# CMCD_and_buckmod_FINAL.net
KiCad netlist of a schematic drawn in EAGLE
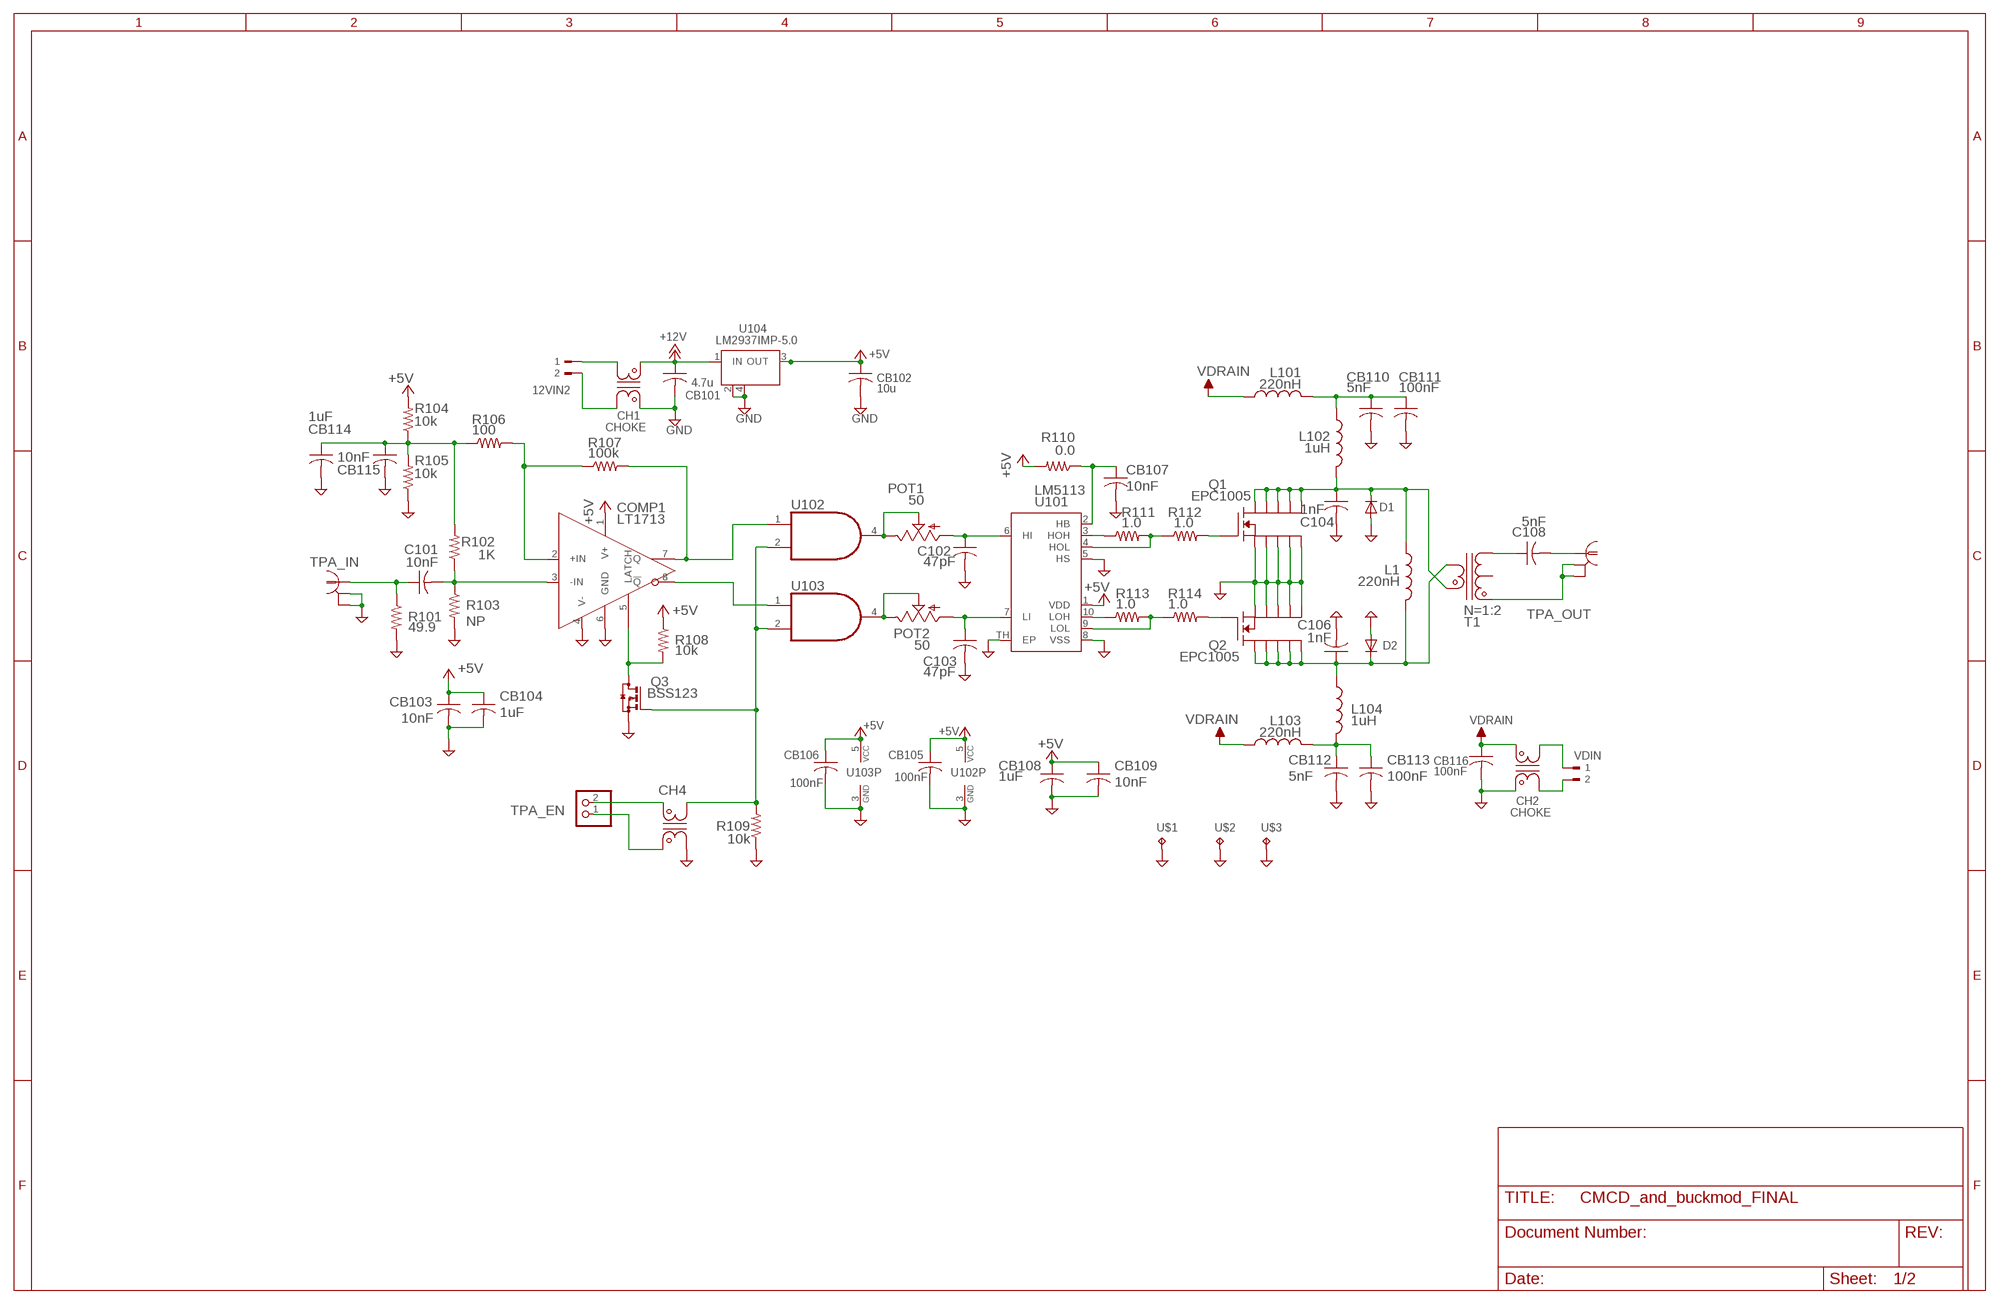
[diagram p0: schematic, sheet 1]
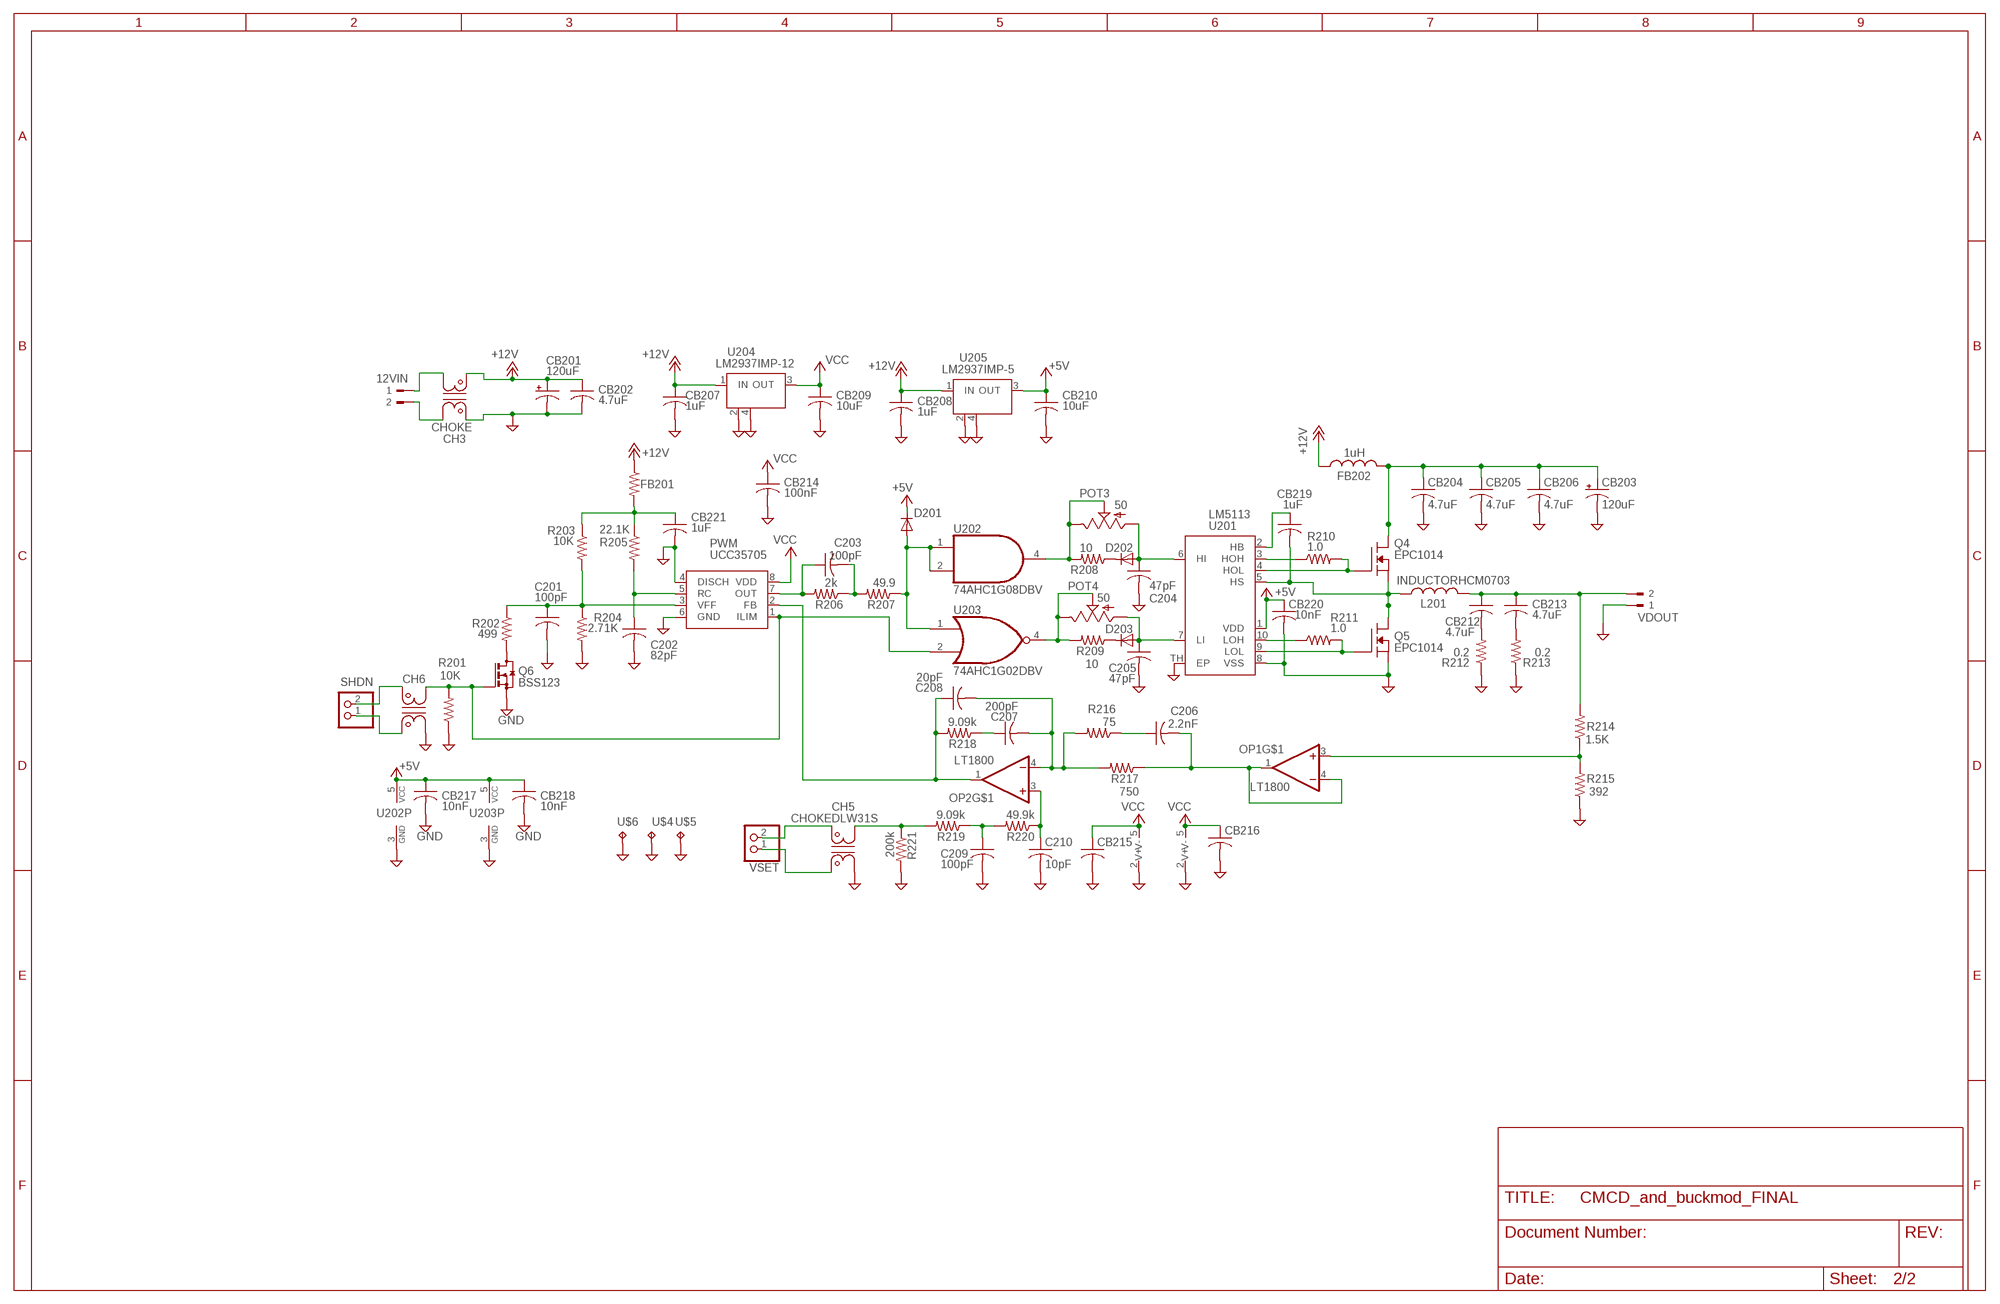
[diagram p1: schematic, sheet 2]

(export (version "E")
  (design (tool "Eeschema 10.0.6"))
  (components
    (comp (ref "12VIN2")
      (value "TERM-2OMNIMATE_SL")
      (footprint "eagle-import:OMNIMATE_SL_2POS")
      (libsource (lib "eagle-import") (part "TERM-2OMNIMATE_SL"))
    )
    (comp (ref "C101")
      (value "10nF")
      (footprint "eagle-import:C0805")
      (libsource (lib "eagle-import") (part "C-USC0805"))
    )
    (comp (ref "C102")
      (value "47pF")
      (footprint "eagle-import:C0805")
      (libsource (lib "eagle-import") (part "C-USC0805"))
    )
    (comp (ref "C103")
      (value "47pF")
      (footprint "eagle-import:C0805")
      (libsource (lib "eagle-import") (part "C-USC0805"))
    )
    (comp (ref "C104")
      (value "1nF")
      (footprint "eagle-import:1008")
      (libsource (lib "eagle-import") (part "CAPACITOR1008"))
    )
    (comp (ref "C106")
      (value "1nF")
      (footprint "eagle-import:1008")
      (libsource (lib "eagle-import") (part "CAPACITOR1008"))
    )
    (comp (ref "C108")
      (value "5nF")
      (footprint "eagle-import:1008")
      (libsource (lib "eagle-import") (part "CAPACITOR1008"))
    )
    (comp (ref "CB101")
      (value "4.7u")
      (footprint "eagle-import:C0805")
      (libsource (lib "eagle-import") (part "C-USC0805"))
    )
    (comp (ref "CB102")
      (value "10u")
      (footprint "eagle-import:C0805")
      (libsource (lib "eagle-import") (part "C-USC0805"))
    )
    (comp (ref "CB103")
      (value "10nF")
      (footprint "eagle-import:C0603")
      (libsource (lib "eagle-import") (part "C-USC0603"))
    )
    (comp (ref "CB104")
      (value "1uF")
      (footprint "eagle-import:C0603")
      (libsource (lib "eagle-import") (part "C-USC0603"))
    )
    (comp (ref "CB105")
      (value "100nF")
      (footprint "eagle-import:C0603")
      (libsource (lib "eagle-import") (part "C-USC0603"))
    )
    (comp (ref "CB106")
      (value "100nF")
      (footprint "eagle-import:C0603")
      (libsource (lib "eagle-import") (part "C-USC0603"))
    )
    (comp (ref "CB107")
      (value "10nF")
      (footprint "eagle-import:C0603")
      (libsource (lib "eagle-import") (part "C-USC0603"))
    )
    (comp (ref "CB108")
      (value "1uF")
      (footprint "eagle-import:C0603")
      (libsource (lib "eagle-import") (part "C-USC0603"))
    )
    (comp (ref "CB109")
      (value "10nF")
      (footprint "eagle-import:C0603")
      (libsource (lib "eagle-import") (part "C-USC0603"))
    )
    (comp (ref "CB110")
      (value "5nF")
      (footprint "eagle-import:1008")
      (libsource (lib "eagle-import") (part "CAPACITOR1008"))
    )
    (comp (ref "CB111")
      (value "100nF")
      (footprint "eagle-import:C0805")
      (libsource (lib "eagle-import") (part "C-USC0805"))
    )
    (comp (ref "CB112")
      (value "5nF")
      (footprint "eagle-import:1008")
      (libsource (lib "eagle-import") (part "CAPACITOR1008"))
    )
    (comp (ref "CB113")
      (value "100nF")
      (footprint "eagle-import:C0805")
      (libsource (lib "eagle-import") (part "C-USC0805"))
    )
    (comp (ref "CB114")
      (value "1uF")
      (footprint "eagle-import:C0805")
      (libsource (lib "eagle-import") (part "C-USC0805"))
    )
    (comp (ref "CB115")
      (value "10nF")
      (footprint "eagle-import:C0603")
      (libsource (lib "eagle-import") (part "C-USC0603"))
    )
    (comp (ref "CB116")
      (value "100nF")
      (footprint "eagle-import:C0805")
      (libsource (lib "eagle-import") (part "C-USC0805"))
    )
    (comp (ref "CH1")
      (value "CHOKE")
      (footprint "eagle-import:CHOKE_DLW5BT")
      (libsource (lib "eagle-import") (part "CHOKE"))
    )
    (comp (ref "CH2")
      (value "CHOKE")
      (footprint "eagle-import:CHOKE_DLW5BT")
      (libsource (lib "eagle-import") (part "CHOKE"))
    )
    (comp (ref "CH4")
      (value "CHOKEDLW31S")
      (footprint "eagle-import:CHOKE_DLW31S")
      (libsource (lib "eagle-import") (part "CHOKEDLW31S"))
    )
    (comp (ref "COMP1")
      (value "LT1713")
      (footprint "eagle-import:MSOP-8")
      (libsource (lib "eagle-import") (part "LT1713"))
    )
    (comp (ref "D1")
      (value "DIODE-DO214AC")
      (footprint "eagle-import:DO214AC")
      (libsource (lib "eagle-import") (part "DIODE-DO214AC"))
    )
    (comp (ref "D2")
      (value "DIODE-DO214AC")
      (footprint "eagle-import:DO214AC")
      (libsource (lib "eagle-import") (part "DIODE-DO214AC"))
    )
    (comp (ref "L1")
      (value "220nH")
      (footprint "eagle-import:GENERAL-1")
      (libsource (lib "eagle-import") (part "amyparts-rf-combined_INDUCTOR"))
    )
    (comp (ref "L101")
      (value "220nH")
      (footprint "eagle-import:GENERAL-1")
      (libsource (lib "eagle-import") (part "amyparts-rf-combined_INDUCTOR"))
    )
    (comp (ref "L102")
      (value "1uH")
      (footprint "eagle-import:GENERAL-1")
      (libsource (lib "eagle-import") (part "amyparts-rf-combined_INDUCTOR"))
    )
    (comp (ref "L103")
      (value "220nH")
      (footprint "eagle-import:GENERAL-1")
      (libsource (lib "eagle-import") (part "amyparts-rf-combined_INDUCTOR"))
    )
    (comp (ref "L104")
      (value "1uH")
      (footprint "eagle-import:GENERAL-1")
      (libsource (lib "eagle-import") (part "amyparts-rf-combined_INDUCTOR"))
    )
    (comp (ref "POT1")
      (value "50")
      (footprint "eagle-import:3223W")
      (libsource (lib "eagle-import") (part "TRIM_US-3223W"))
    )
    (comp (ref "POT2")
      (value "50")
      (footprint "eagle-import:3223W")
      (libsource (lib "eagle-import") (part "TRIM_US-3223W"))
    )
    (comp (ref "Q1")
      (value "EPC1005")
      (footprint "eagle-import:11-LGA")
      (libsource (lib "eagle-import") (part "EPC1005"))
    )
    (comp (ref "Q2")
      (value "EPC1005")
      (footprint "eagle-import:11-LGA")
      (libsource (lib "eagle-import") (part "EPC1005"))
    )
    (comp (ref "Q3")
      (value "BSS123")
      (footprint "eagle-import:SOT23")
      (libsource (lib "eagle-import") (part "BSS123"))
    )
    (comp (ref "R101")
      (value "49.9")
      (footprint "eagle-import:R0805")
      (libsource (lib "eagle-import") (part "R-US_R0805"))
    )
    (comp (ref "R102")
      (value "1K")
      (footprint "eagle-import:R0805")
      (libsource (lib "eagle-import") (part "R-US_R0805"))
    )
    (comp (ref "R103")
      (value "NP")
      (footprint "eagle-import:R0805")
      (libsource (lib "eagle-import") (part "R-US_R0805"))
    )
    (comp (ref "R104")
      (value "10k")
      (footprint "eagle-import:R0805")
      (libsource (lib "eagle-import") (part "R-US_R0805"))
    )
    (comp (ref "R105")
      (value "10k")
      (footprint "eagle-import:R0805")
      (libsource (lib "eagle-import") (part "R-US_R0805"))
    )
    (comp (ref "R106")
      (value "100")
      (footprint "eagle-import:R0805")
      (libsource (lib "eagle-import") (part "R-US_R0805"))
    )
    (comp (ref "R107")
      (value "100k")
      (footprint "eagle-import:R0805")
      (libsource (lib "eagle-import") (part "R-US_R0805"))
    )
    (comp (ref "R108")
      (value "10k")
      (footprint "eagle-import:R0805")
      (libsource (lib "eagle-import") (part "R-US_R0805"))
    )
    (comp (ref "R109")
      (value "10k")
      (footprint "eagle-import:R0805")
      (libsource (lib "eagle-import") (part "R-US_R0805"))
    )
    (comp (ref "R110")
      (value "0.0")
      (footprint "eagle-import:R0603")
      (libsource (lib "eagle-import") (part "R-US_R0603"))
    )
    (comp (ref "R111")
      (value "1.0")
      (footprint "eagle-import:R0603")
      (libsource (lib "eagle-import") (part "R-US_R0603"))
    )
    (comp (ref "R112")
      (value "1.0")
      (footprint "eagle-import:R0603")
      (libsource (lib "eagle-import") (part "R-US_R0603"))
    )
    (comp (ref "R113")
      (value "1.0")
      (footprint "eagle-import:R0603")
      (libsource (lib "eagle-import") (part "R-US_R0603"))
    )
    (comp (ref "R114")
      (value "1.0")
      (footprint "eagle-import:R0603")
      (libsource (lib "eagle-import") (part "R-US_R0603"))
    )
    (comp (ref "T1")
      (value "N=1:2")
      (footprint "eagle-import:BALUN_GENERAL_BIG")
      (libsource (lib "eagle-import") (part "BALUN_2{colon}1BALUN_CUSTOM_BIG"))
    )
    (comp (ref "TPA_EN")
      (value "PINHD-1X2")
      (footprint "eagle-import:1X02")
      (libsource (lib "eagle-import") (part "PINHD-1X2"))
    )
    (comp (ref "TPA_IN")
      (value "BNC-EDGE")
      (footprint "eagle-import:BNC-EDGE")
      (libsource (lib "eagle-import") (part "BNC-EDGE"))
    )
    (comp (ref "TPA_OUT")
      (value "BNC-EDGE")
      (footprint "eagle-import:BNC-EDGE")
      (libsource (lib "eagle-import") (part "BNC-EDGE"))
    )
    (comp (ref "U$1")
      (value "TESTPOINTKEYSTONE_ELECTRONICS_5016")
      (footprint "eagle-import:SMD_TESTPAD")
      (libsource (lib "eagle-import") (part "TESTPOINTKEYSTONE_ELECTRONICS_5016"))
    )
    (comp (ref "U$2")
      (value "TESTPOINTKEYSTONE_ELECTRONICS_5016")
      (footprint "eagle-import:SMD_TESTPAD")
      (libsource (lib "eagle-import") (part "TESTPOINTKEYSTONE_ELECTRONICS_5016"))
    )
    (comp (ref "U$3")
      (value "TESTPOINTKEYSTONE_ELECTRONICS_5016")
      (footprint "eagle-import:SMD_TESTPAD")
      (libsource (lib "eagle-import") (part "TESTPOINTKEYSTONE_ELECTRONICS_5016"))
    )
    (comp (ref "U101")
      (value "LM5113")
      (footprint "eagle-import:LLP-10")
      (libsource (lib "eagle-import") (part "amyparts-rf-combined_LM5113"))
    )
    (comp (ref "U102")
      (value "74AHC1G08DBV")
      (footprint "eagle-import:SOT23-5")
      (libsource (lib "eagle-import") (part "741G08DBVAHC"))
    )
    (comp (ref "U103")
      (value "74AHC1G08DBV")
      (footprint "eagle-import:SOT23-5")
      (libsource (lib "eagle-import") (part "741G08DBVAHC"))
    )
    (comp (ref "U104")
      (value "LM2937IMP-5.0")
      (footprint "eagle-import:SOT223")
      (libsource (lib "eagle-import") (part "LM340S"))
    )
    (comp (ref "VDIN")
      (value "TERM-2OMNIMATE_SL")
      (footprint "eagle-import:OMNIMATE_SL_2POS")
      (libsource (lib "eagle-import") (part "TERM-2OMNIMATE_SL"))
    )
    (comp (ref "12VIN")
      (value "TERM-2OMNIMATE_SL")
      (footprint "eagle-import:OMNIMATE_SL_2POS")
      (libsource (lib "eagle-import") (part "TERM-2OMNIMATE_SL"))
    )
    (comp (ref "C201")
      (value "100pF")
      (footprint "eagle-import:C0805")
      (libsource (lib "eagle-import") (part "C-USC0805"))
    )
    (comp (ref "C202")
      (value "82pF")
      (footprint "eagle-import:C0805")
      (libsource (lib "eagle-import") (part "C-USC0805"))
    )
    (comp (ref "C203")
      (value "100pF")
      (footprint "eagle-import:C0805")
      (libsource (lib "eagle-import") (part "C-USC0805"))
    )
    (comp (ref "C204")
      (value "47pF")
      (footprint "eagle-import:C0603")
      (libsource (lib "eagle-import") (part "C-USC0603"))
    )
    (comp (ref "C205")
      (value "47pF")
      (footprint "eagle-import:C0603")
      (libsource (lib "eagle-import") (part "C-USC0603"))
    )
    (comp (ref "C206")
      (value "2.2nF")
      (footprint "eagle-import:C0805")
      (libsource (lib "eagle-import") (part "C-USC0805"))
    )
    (comp (ref "C207")
      (value "200pF")
      (footprint "eagle-import:C0805")
      (libsource (lib "eagle-import") (part "C-USC0805"))
    )
    (comp (ref "C208")
      (value "20pF")
      (footprint "eagle-import:C0805")
      (libsource (lib "eagle-import") (part "C-USC0805"))
    )
    (comp (ref "C209")
      (value "100pF")
      (footprint "eagle-import:C0805")
      (libsource (lib "eagle-import") (part "C-USC0805"))
    )
    (comp (ref "C210")
      (value "10pF")
      (footprint "eagle-import:C0805")
      (libsource (lib "eagle-import") (part "C-USC0805"))
    )
    (comp (ref "CB201")
      (value "120uF")
      (footprint "eagle-import:E3,5-8")
      (libsource (lib "eagle-import") (part "CPOL-USE3.5-8"))
    )
    (comp (ref "CB202")
      (value "4.7uF")
      (footprint "eagle-import:C0805")
      (libsource (lib "eagle-import") (part "C-USC0805"))
    )
    (comp (ref "CB203")
      (value "120uF")
      (footprint "eagle-import:E3,5-8")
      (libsource (lib "eagle-import") (part "CPOL-USE3.5-8"))
    )
    (comp (ref "CB204")
      (value "4.7uF")
      (footprint "eagle-import:C0805")
      (libsource (lib "eagle-import") (part "C-USC0805"))
    )
    (comp (ref "CB205")
      (value "4.7uF")
      (footprint "eagle-import:1206-LONG")
      (libsource (lib "eagle-import") (part "CAPACITOR1206-LONG"))
    )
    (comp (ref "CB206")
      (value "4.7uF")
      (footprint "eagle-import:1206-LONG")
      (libsource (lib "eagle-import") (part "CAPACITOR1206-LONG"))
    )
    (comp (ref "CB207")
      (value "1uF")
      (footprint "eagle-import:C0805")
      (libsource (lib "eagle-import") (part "C-USC0805"))
    )
    (comp (ref "CB208")
      (value "1uF")
      (footprint "eagle-import:C0805")
      (libsource (lib "eagle-import") (part "C-USC0805"))
    )
    (comp (ref "CB209")
      (value "10uF")
      (footprint "eagle-import:C0805")
      (libsource (lib "eagle-import") (part "C-USC0805"))
    )
    (comp (ref "CB210")
      (value "10uF")
      (footprint "eagle-import:C0805")
      (libsource (lib "eagle-import") (part "C-USC0805"))
    )
    (comp (ref "CB212")
      (value "4.7uF")
      (footprint "eagle-import:C0805")
      (libsource (lib "eagle-import") (part "C-USC0805"))
    )
    (comp (ref "CB213")
      (value "4.7uF")
      (footprint "eagle-import:C0805")
      (libsource (lib "eagle-import") (part "C-USC0805"))
    )
    (comp (ref "CB214")
      (value "100nF")
      (footprint "eagle-import:C0603")
      (libsource (lib "eagle-import") (part "C-USC0603"))
    )
    (comp (ref "CB215")
      (value "C-USC0603")
      (footprint "eagle-import:C0603")
      (libsource (lib "eagle-import") (part "C-USC0603"))
    )
    (comp (ref "CB216")
      (value "C-USC0603")
      (footprint "eagle-import:C0603")
      (libsource (lib "eagle-import") (part "C-USC0603"))
    )
    (comp (ref "CB217")
      (value "10nF")
      (footprint "eagle-import:C0603")
      (libsource (lib "eagle-import") (part "C-USC0603"))
    )
    (comp (ref "CB218")
      (value "10nF")
      (footprint "eagle-import:C0603")
      (libsource (lib "eagle-import") (part "C-USC0603"))
    )
    (comp (ref "CB219")
      (value "1uF")
      (footprint "eagle-import:C0603")
      (libsource (lib "eagle-import") (part "C-USC0603"))
    )
    (comp (ref "CB220")
      (value "10nF")
      (footprint "eagle-import:C0603")
      (libsource (lib "eagle-import") (part "C-USC0603"))
    )
    (comp (ref "CB221")
      (value "1uF")
      (footprint "eagle-import:C0805")
      (libsource (lib "eagle-import") (part "C-USC0805"))
    )
    (comp (ref "CH3")
      (value "CHOKE")
      (footprint "eagle-import:CHOKE_DLW5BT")
      (libsource (lib "eagle-import") (part "CHOKE"))
    )
    (comp (ref "CH5")
      (value "CHOKEDLW31S")
      (footprint "eagle-import:CHOKE_DLW31S")
      (libsource (lib "eagle-import") (part "CHOKEDLW31S"))
    )
    (comp (ref "CH6")
      (value "CHOKEDLW31S")
      (footprint "eagle-import:CHOKE_DLW31S")
      (libsource (lib "eagle-import") (part "CHOKEDLW31S"))
    )
    (comp (ref "D201")
      (value "DIODE-SOD323-W")
      (footprint "eagle-import:SOD323-W")
      (libsource (lib "eagle-import") (part "DIODE-SOD323-W"))
    )
    (comp (ref "D202")
      (value "DIODE-SOD323-W")
      (footprint "eagle-import:SOD323-W")
      (libsource (lib "eagle-import") (part "DIODE-SOD323-W"))
    )
    (comp (ref "D203")
      (value "DIODE-SOD323-W")
      (footprint "eagle-import:SOD323-W")
      (libsource (lib "eagle-import") (part "DIODE-SOD323-W"))
    )
    (comp (ref "FB201")
      (value "R-US_R0805")
      (footprint "eagle-import:R0805")
      (libsource (lib "eagle-import") (part "R-US_R0805"))
    )
    (comp (ref "FB202")
      (value "1uH")
      (footprint "eagle-import:1008")
      (libsource (lib "eagle-import") (part "INDUCTOR1008"))
    )
    (comp (ref "L201")
      (value "INDUCTORHCM0703")
      (footprint "eagle-import:HCM0703")
      (libsource (lib "eagle-import") (part "INDUCTORHCM0703"))
    )
    (comp (ref "OP1")
      (value "LT1800")
      (footprint "eagle-import:SOT23-5")
      (libsource (lib "eagle-import") (part "LMH6624"))
    )
    (comp (ref "OP2")
      (value "LT1800")
      (footprint "eagle-import:SOT23-5")
      (libsource (lib "eagle-import") (part "LMH6624"))
    )
    (comp (ref "POT3")
      (value "50")
      (footprint "eagle-import:3223W")
      (libsource (lib "eagle-import") (part "TRIM_US-3223W"))
    )
    (comp (ref "POT4")
      (value "50")
      (footprint "eagle-import:3223W")
      (libsource (lib "eagle-import") (part "TRIM_US-3223W"))
    )
    (comp (ref "PWM")
      (value "UCC35705")
      (footprint "eagle-import:MSOP-8")
      (libsource (lib "eagle-import") (part "UCC35705"))
    )
    (comp (ref "Q4")
      (value "EPC1014")
      (footprint "eagle-import:5-LGA")
      (libsource (lib "eagle-import") (part "EPC1014"))
    )
    (comp (ref "Q5")
      (value "EPC1014")
      (footprint "eagle-import:5-LGA")
      (libsource (lib "eagle-import") (part "EPC1014"))
    )
    (comp (ref "Q6")
      (value "BSS123")
      (footprint "eagle-import:SOT23")
      (libsource (lib "eagle-import") (part "BSS123"))
    )
    (comp (ref "R201")
      (value "10K")
      (footprint "eagle-import:R0805")
      (libsource (lib "eagle-import") (part "R-US_R0805"))
    )
    (comp (ref "R202")
      (value "499")
      (footprint "eagle-import:R0805")
      (libsource (lib "eagle-import") (part "R-US_R0805"))
    )
    (comp (ref "R203")
      (value "10K")
      (footprint "eagle-import:R0805")
      (libsource (lib "eagle-import") (part "R-US_R0805"))
    )
    (comp (ref "R204")
      (value "2.71K")
      (footprint "eagle-import:R0805")
      (libsource (lib "eagle-import") (part "R-US_R0805"))
    )
    (comp (ref "R205")
      (value "22.1K")
      (footprint "eagle-import:R0805")
      (libsource (lib "eagle-import") (part "R-US_R0805"))
    )
    (comp (ref "R206")
      (value "2k")
      (footprint "eagle-import:R0805")
      (libsource (lib "eagle-import") (part "R-US_R0805"))
    )
    (comp (ref "R207")
      (value "49.9")
      (footprint "eagle-import:R0805")
      (libsource (lib "eagle-import") (part "R-US_R0805"))
    )
    (comp (ref "R208")
      (value "10")
      (footprint "eagle-import:R0805")
      (libsource (lib "eagle-import") (part "R-US_R0805"))
    )
    (comp (ref "R209")
      (value "10")
      (footprint "eagle-import:R0805")
      (libsource (lib "eagle-import") (part "R-US_R0805"))
    )
    (comp (ref "R210")
      (value "1.0")
      (footprint "eagle-import:R0603")
      (libsource (lib "eagle-import") (part "R-US_R0603"))
    )
    (comp (ref "R211")
      (value "1.0")
      (footprint "eagle-import:R0603")
      (libsource (lib "eagle-import") (part "R-US_R0603"))
    )
    (comp (ref "R212")
      (value "0.2")
      (footprint "eagle-import:R0805")
      (libsource (lib "eagle-import") (part "R-US_R0805"))
    )
    (comp (ref "R213")
      (value "0.2")
      (footprint "eagle-import:R0805")
      (libsource (lib "eagle-import") (part "R-US_R0805"))
    )
    (comp (ref "R214")
      (value "1.5K")
      (footprint "eagle-import:R0805")
      (libsource (lib "eagle-import") (part "R-US_R0805"))
    )
    (comp (ref "R215")
      (value "392")
      (footprint "eagle-import:R0805")
      (libsource (lib "eagle-import") (part "R-US_R0805"))
    )
    (comp (ref "R216")
      (value "75")
      (footprint "eagle-import:R0805")
      (libsource (lib "eagle-import") (part "R-US_R0805"))
    )
    (comp (ref "R217")
      (value "750")
      (footprint "eagle-import:R0805")
      (libsource (lib "eagle-import") (part "R-US_R0805"))
    )
    (comp (ref "R218")
      (value "9.09k")
      (footprint "eagle-import:R0805")
      (libsource (lib "eagle-import") (part "R-US_R0805"))
    )
    (comp (ref "R219")
      (value "9.09k")
      (footprint "eagle-import:R0805")
      (libsource (lib "eagle-import") (part "R-US_R0805"))
    )
    (comp (ref "R220")
      (value "49.9k")
      (footprint "eagle-import:R0805")
      (libsource (lib "eagle-import") (part "R-US_R0805"))
    )
    (comp (ref "R221")
      (value "200k")
      (footprint "eagle-import:R0805")
      (libsource (lib "eagle-import") (part "R-US_R0805"))
    )
    (comp (ref "SHDN")
      (value "PINHD-1X2")
      (footprint "eagle-import:1X02")
      (libsource (lib "eagle-import") (part "PINHD-1X2"))
    )
    (comp (ref "U$4")
      (value "TESTPOINTKEYSTONE_ELECTRONICS_5016")
      (footprint "eagle-import:SMD_TESTPAD")
      (libsource (lib "eagle-import") (part "TESTPOINTKEYSTONE_ELECTRONICS_5016"))
    )
    (comp (ref "U$5")
      (value "TESTPOINTKEYSTONE_ELECTRONICS_5016")
      (footprint "eagle-import:SMD_TESTPAD")
      (libsource (lib "eagle-import") (part "TESTPOINTKEYSTONE_ELECTRONICS_5016"))
    )
    (comp (ref "U$6")
      (value "TESTPOINTKEYSTONE_ELECTRONICS_5016")
      (footprint "eagle-import:SMD_TESTPAD")
      (libsource (lib "eagle-import") (part "TESTPOINTKEYSTONE_ELECTRONICS_5016"))
    )
    (comp (ref "U201")
      (value "LM5113")
      (footprint "eagle-import:LLP-10")
      (libsource (lib "eagle-import") (part "LM5113"))
    )
    (comp (ref "U202")
      (value "74AHC1G08DBV")
      (footprint "eagle-import:SOT23-5")
      (libsource (lib "eagle-import") (part "741G08DBVAHC"))
    )
    (comp (ref "U203")
      (value "74AHC1G02DBV")
      (footprint "eagle-import:SOT23-5")
      (libsource (lib "eagle-import") (part "741G02DBVAHC"))
    )
    (comp (ref "U204")
      (value "LM2937IMP-12")
      (footprint "eagle-import:SOT223")
      (libsource (lib "eagle-import") (part "LM340S"))
    )
    (comp (ref "U205")
      (value "LM2937IMP-5")
      (footprint "eagle-import:SOT223")
      (libsource (lib "eagle-import") (part "LM340S"))
    )
    (comp (ref "VDOUT")
      (value "TERM-2OMNIMATE_SL")
      (footprint "eagle-import:OMNIMATE_SL_2POS")
      (libsource (lib "eagle-import") (part "TERM-2OMNIMATE_SL"))
    )
    (comp (ref "VSET")
      (value "PINHD-1X2")
      (footprint "eagle-import:1X02")
      (libsource (lib "eagle-import") (part "PINHD-1X2"))
    )
  )
  (nets
    (net (code "1") (name "+5V") (class "Default")
      (node (ref "CB102") (pin "1") (pinfunction "1_1") (pintype "passive"))
      (node (ref "CB103") (pin "1") (pinfunction "1_1") (pintype "passive"))
      (node (ref "CB104") (pin "1") (pinfunction "1_1") (pintype "passive"))
      (node (ref "CB105") (pin "1") (pinfunction "1_1") (pintype "passive"))
      (node (ref "CB106") (pin "1") (pinfunction "1_1") (pintype "passive"))
      (node (ref "CB108") (pin "1") (pinfunction "1_1") (pintype "passive"))
      (node (ref "CB109") (pin "1") (pinfunction "1_1") (pintype "passive"))
      (node (ref "CB210") (pin "1") (pinfunction "1_1") (pintype "passive"))
      (node (ref "CB217") (pin "1") (pinfunction "1_1") (pintype "passive"))
      (node (ref "CB218") (pin "1") (pinfunction "1_1") (pintype "passive"))
      (node (ref "CB220") (pin "1") (pinfunction "1_1") (pintype "passive"))
      (node (ref "COMP1") (pin "1") (pinfunction "V+_1") (pintype "power_in"))
      (node (ref "D201") (pin "C") (pinfunction "C_C") (pintype "passive"))
      (node (ref "R104") (pin "2") (pinfunction "2_2") (pintype "passive"))
      (node (ref "R108") (pin "1") (pinfunction "1_1") (pintype "passive"))
      (node (ref "R110") (pin "2") (pinfunction "2_2") (pintype "passive"))
      (node (ref "U101") (pin "1") (pinfunction "VDD_1") (pintype "power_in"))
      (node (ref "U102") (pin "5") (pinfunction "VCC_5") (pintype "power_in"))
      (node (ref "U103") (pin "5") (pinfunction "VCC_5") (pintype "power_in"))
      (node (ref "U104") (pin "3") (pinfunction "OUT_3") (pintype "passive"))
      (node (ref "U201") (pin "1") (pinfunction "VDD_1") (pintype "power_in"))
      (node (ref "U202") (pin "5") (pinfunction "VCC_5") (pintype "power_in"))
      (node (ref "U203") (pin "5") (pinfunction "VCC_5") (pintype "power_in"))
      (node (ref "U205") (pin "3") (pinfunction "OUT_3") (pintype "passive"))
    )
    (net (code "2") (name "+12V") (class "Default")
      (node (ref "CB101") (pin "1") (pinfunction "1_1") (pintype "passive"))
      (node (ref "CB201") (pin "+") (pinfunction "+_+") (pintype "passive"))
      (node (ref "CB202") (pin "1") (pinfunction "1_1") (pintype "passive"))
      (node (ref "CB207") (pin "1") (pinfunction "1_1") (pintype "passive"))
      (node (ref "CB208") (pin "1") (pinfunction "1_1") (pintype "passive"))
      (node (ref "CH1") (pin "P$4") (pinfunction "4_P$4") (pintype "passive"))
      (node (ref "CH3") (pin "P$4") (pinfunction "4_P$4") (pintype "passive"))
      (node (ref "FB201") (pin "1") (pinfunction "1_1") (pintype "passive"))
      (node (ref "FB202") (pin "P$1") (pinfunction "1_P$1") (pintype "passive"))
      (node (ref "U104") (pin "1") (pinfunction "IN_1") (pintype "input"))
      (node (ref "U204") (pin "1") (pinfunction "IN_1") (pintype "input"))
      (node (ref "U205") (pin "1") (pinfunction "IN_1") (pintype "input"))
    )
    (net (code "3") (name "GND") (class "Default")
      (node (ref "C102") (pin "2") (pinfunction "2_2") (pintype "passive"))
      (node (ref "C103") (pin "2") (pinfunction "2_2") (pintype "passive"))
      (node (ref "C104") (pin "P$2") (pinfunction "2_P$2") (pintype "passive"))
      (node (ref "C106") (pin "P$2") (pinfunction "2_P$2") (pintype "passive"))
      (node (ref "C201") (pin "2") (pinfunction "2_2") (pintype "passive"))
      (node (ref "C202") (pin "2") (pinfunction "2_2") (pintype "passive"))
      (node (ref "C204") (pin "2") (pinfunction "2_2") (pintype "passive"))
      (node (ref "C205") (pin "2") (pinfunction "2_2") (pintype "passive"))
      (node (ref "C209") (pin "2") (pinfunction "2_2") (pintype "passive"))
      (node (ref "C210") (pin "2") (pinfunction "2_2") (pintype "passive"))
      (node (ref "CB101") (pin "2") (pinfunction "2_2") (pintype "passive"))
      (node (ref "CB102") (pin "2") (pinfunction "2_2") (pintype "passive"))
      (node (ref "CB103") (pin "2") (pinfunction "2_2") (pintype "passive"))
      (node (ref "CB104") (pin "2") (pinfunction "2_2") (pintype "passive"))
      (node (ref "CB105") (pin "2") (pinfunction "2_2") (pintype "passive"))
      (node (ref "CB106") (pin "2") (pinfunction "2_2") (pintype "passive"))
      (node (ref "CB107") (pin "2") (pinfunction "2_2") (pintype "passive"))
      (node (ref "CB108") (pin "2") (pinfunction "2_2") (pintype "passive"))
      (node (ref "CB109") (pin "2") (pinfunction "2_2") (pintype "passive"))
      (node (ref "CB110") (pin "P$2") (pinfunction "2_P$2") (pintype "passive"))
      (node (ref "CB111") (pin "2") (pinfunction "2_2") (pintype "passive"))
      (node (ref "CB112") (pin "P$2") (pinfunction "2_P$2") (pintype "passive"))
      (node (ref "CB113") (pin "2") (pinfunction "2_2") (pintype "passive"))
      (node (ref "CB114") (pin "2") (pinfunction "2_2") (pintype "passive"))
      (node (ref "CB115") (pin "2") (pinfunction "2_2") (pintype "passive"))
      (node (ref "CB116") (pin "2") (pinfunction "2_2") (pintype "passive"))
      (node (ref "CB201") (pin "-") (pinfunction "-_-") (pintype "passive"))
      (node (ref "CB202") (pin "2") (pinfunction "2_2") (pintype "passive"))
      (node (ref "CB203") (pin "-") (pinfunction "-_-") (pintype "passive"))
      (node (ref "CB204") (pin "2") (pinfunction "2_2") (pintype "passive"))
      (node (ref "CB205") (pin "2") (pinfunction "2_2") (pintype "passive"))
      (node (ref "CB206") (pin "2") (pinfunction "2_2") (pintype "passive"))
      (node (ref "CB207") (pin "2") (pinfunction "2_2") (pintype "passive"))
      (node (ref "CB208") (pin "2") (pinfunction "2_2") (pintype "passive"))
      (node (ref "CB209") (pin "2") (pinfunction "2_2") (pintype "passive"))
      (node (ref "CB210") (pin "2") (pinfunction "2_2") (pintype "passive"))
      (node (ref "CB214") (pin "2") (pinfunction "2_2") (pintype "passive"))
      (node (ref "CB215") (pin "2") (pinfunction "2_2") (pintype "passive"))
      (node (ref "CB216") (pin "2") (pinfunction "2_2") (pintype "passive"))
      (node (ref "CB217") (pin "2") (pinfunction "2_2") (pintype "passive"))
      (node (ref "CB218") (pin "2") (pinfunction "2_2") (pintype "passive"))
      (node (ref "CB220") (pin "2") (pinfunction "2_2") (pintype "passive"))
      (node (ref "CB221") (pin "2") (pinfunction "2_2") (pintype "passive"))
      (node (ref "CH1") (pin "P$1") (pinfunction "1_P$1") (pintype "passive"))
      (node (ref "CH2") (pin "P$1") (pinfunction "1_P$1") (pintype "passive"))
      (node (ref "CH3") (pin "P$1") (pinfunction "1_P$1") (pintype "passive"))
      (node (ref "CH4") (pin "P$2") (pinfunction "2_P$2") (pintype "passive"))
      (node (ref "CH5") (pin "P$2") (pinfunction "2_P$2") (pintype "passive"))
      (node (ref "CH6") (pin "P$2") (pinfunction "2_P$2") (pintype "passive"))
      (node (ref "COMP1") (pin "4") (pinfunction "V-_4") (pintype "power_in"))
      (node (ref "COMP1") (pin "6") (pinfunction "GND_6") (pintype "power_in"))
      (node (ref "D1") (pin "A") (pinfunction "A_A") (pintype "passive"))
      (node (ref "D2") (pin "A") (pinfunction "A_A") (pintype "passive"))
      (node (ref "OP1") (pin "2") (pinfunction "V-_2") (pintype "power_in"))
      (node (ref "OP2") (pin "2") (pinfunction "V-_2") (pintype "power_in"))
      (node (ref "PWM") (pin "4") (pinfunction "DISCH_4") (pintype "passive"))
      (node (ref "PWM") (pin "6") (pinfunction "GND_6") (pintype "power_in"))
      (node (ref "Q1") (pin "10") (pinfunction "S5_10") (pintype "passive"))
      (node (ref "Q1") (pin "2") (pinfunction "S1_2") (pintype "passive"))
      (node (ref "Q1") (pin "4") (pinfunction "S2_4") (pintype "passive"))
      (node (ref "Q1") (pin "6") (pinfunction "S3_6") (pintype "passive"))
      (node (ref "Q1") (pin "8") (pinfunction "S4_8") (pintype "passive"))
      (node (ref "Q2") (pin "10") (pinfunction "S5_10") (pintype "passive"))
      (node (ref "Q2") (pin "2") (pinfunction "S1_2") (pintype "passive"))
      (node (ref "Q2") (pin "4") (pinfunction "S2_4") (pintype "passive"))
      (node (ref "Q2") (pin "6") (pinfunction "S3_6") (pintype "passive"))
      (node (ref "Q2") (pin "8") (pinfunction "S4_8") (pintype "passive"))
      (node (ref "Q3") (pin "2") (pinfunction "S_2") (pintype "passive"))
      (node (ref "Q5") (pin "2") (pinfunction "S1_2") (pintype "passive"))
      (node (ref "Q5") (pin "4") (pinfunction "S2_4") (pintype "passive"))
      (node (ref "Q6") (pin "2") (pinfunction "S_2") (pintype "passive"))
      (node (ref "R101") (pin "2") (pinfunction "2_2") (pintype "passive"))
      (node (ref "R103") (pin "2") (pinfunction "2_2") (pintype "passive"))
      (node (ref "R105") (pin "1") (pinfunction "1_1") (pintype "passive"))
      (node (ref "R109") (pin "1") (pinfunction "1_1") (pintype "passive"))
      (node (ref "R201") (pin "1") (pinfunction "1_1") (pintype "passive"))
      (node (ref "R204") (pin "2") (pinfunction "2_2") (pintype "passive"))
      (node (ref "R212") (pin "1") (pinfunction "1_1") (pintype "passive"))
      (node (ref "R213") (pin "1") (pinfunction "1_1") (pintype "passive"))
      (node (ref "R215") (pin "1") (pinfunction "1_1") (pintype "passive"))
      (node (ref "R221") (pin "2") (pinfunction "2_2") (pintype "passive"))
      (node (ref "TPA_IN") (pin "S1") (pinfunction "GND1_S1") (pintype "power_in"))
      (node (ref "TPA_IN") (pin "S2") (pinfunction "GND2_S2") (pintype "power_in"))
      (node (ref "U$1") (pin "P$1") (pinfunction "TP_P$1") (pintype "input"))
      (node (ref "U$2") (pin "P$1") (pinfunction "TP_P$1") (pintype "input"))
      (node (ref "U$3") (pin "P$1") (pinfunction "TP_P$1") (pintype "input"))
      (node (ref "U$4") (pin "P$1") (pinfunction "TP_P$1") (pintype "input"))
      (node (ref "U$5") (pin "P$1") (pinfunction "TP_P$1") (pintype "input"))
      (node (ref "U$6") (pin "P$1") (pinfunction "TP_P$1") (pintype "input"))
      (node (ref "U101") (pin "5") (pinfunction "HS_5") (pintype "passive"))
      (node (ref "U101") (pin "8") (pinfunction "VSS_8") (pintype "power_in"))
      (node (ref "U101") (pin "TH") (pinfunction "EP_TH") (pintype "power_in"))
      (node (ref "U102") (pin "3") (pinfunction "GND_3") (pintype "power_in"))
      (node (ref "U103") (pin "3") (pinfunction "GND_3") (pintype "power_in"))
      (node (ref "U104") (pin "2") (pinfunction "GND_2") (pintype "power_in"))
      (node (ref "U104") (pin "4") (pinfunction "GND_4") (pintype "power_in"))
      (node (ref "U201") (pin "8") (pinfunction "VSS_8") (pintype "power_in"))
      (node (ref "U201") (pin "TH") (pinfunction "EP_TH") (pintype "power_in"))
      (node (ref "U202") (pin "3") (pinfunction "GND_3") (pintype "power_in"))
      (node (ref "U203") (pin "3") (pinfunction "GND_3") (pintype "power_in"))
      (node (ref "U204") (pin "2") (pinfunction "GND_2") (pintype "power_in"))
      (node (ref "U204") (pin "4") (pinfunction "GND_4") (pintype "power_in"))
      (node (ref "U205") (pin "2") (pinfunction "GND_2") (pintype "power_in"))
      (node (ref "U205") (pin "4") (pinfunction "GND_4") (pintype "power_in"))
      (node (ref "VDOUT") (pin "1") (pinfunction "1_1") (pintype "passive"))
    )
    (net (code "4") (name "Net-(C104-1)") (class "Default")
      (node (ref "C104") (pin "P$1") (pinfunction "1_P$1") (pintype "passive"))
      (node (ref "D1") (pin "C") (pinfunction "C_C") (pintype "passive"))
      (node (ref "L1") (pin "P$1") (pinfunction "1_P$1") (pintype "passive"))
      (node (ref "L102") (pin "P$2") (pinfunction "2_P$2") (pintype "passive"))
      (node (ref "Q1") (pin "11") (pinfunction "D5_11") (pintype "passive"))
      (node (ref "Q1") (pin "3") (pinfunction "D1_3") (pintype "passive"))
      (node (ref "Q1") (pin "5") (pinfunction "D2_5") (pintype "passive"))
      (node (ref "Q1") (pin "7") (pinfunction "D3_7") (pintype "passive"))
      (node (ref "Q1") (pin "9") (pinfunction "D4_9") (pintype "passive"))
      (node (ref "T1") (pin "P1") (pinfunction "1_P1") (pintype "passive"))
    )
    (net (code "5") (name "Net-(C106-1)") (class "Default")
      (node (ref "C106") (pin "P$1") (pinfunction "1_P$1") (pintype "passive"))
      (node (ref "D2") (pin "C") (pinfunction "C_C") (pintype "passive"))
      (node (ref "L1") (pin "P$2") (pinfunction "2_P$2") (pintype "passive"))
      (node (ref "L104") (pin "P$1") (pinfunction "1_P$1") (pintype "passive"))
      (node (ref "Q2") (pin "11") (pinfunction "D5_11") (pintype "passive"))
      (node (ref "Q2") (pin "3") (pinfunction "D1_3") (pintype "passive"))
      (node (ref "Q2") (pin "5") (pinfunction "D2_5") (pintype "passive"))
      (node (ref "Q2") (pin "7") (pinfunction "D3_7") (pintype "passive"))
      (node (ref "Q2") (pin "9") (pinfunction "D4_9") (pintype "passive"))
      (node (ref "T1") (pin "P2") (pinfunction "3_P2") (pintype "passive"))
    )
    (net (code "6") (name "Net-(C108-1)") (class "Default")
      (node (ref "C108") (pin "P$1") (pinfunction "1_P$1") (pintype "passive"))
      (node (ref "T1") (pin "S2") (pinfunction "4_S2") (pintype "passive"))
    )
    (net (code "7") (name "Net-(C108-2)") (class "Default")
      (node (ref "C108") (pin "P$2") (pinfunction "2_P$2") (pintype "passive"))
      (node (ref "TPA_OUT") (pin "I") (pinfunction "1_I") (pintype "passive"))
    )
    (net (code "8") (name "Net-(C203-Pad2)") (class "Default")
      (node (ref "C203") (pin "2") (pinfunction "2_2") (pintype "passive"))
      (node (ref "R206") (pin "1") (pinfunction "1_1") (pintype "passive"))
      (node (ref "R207") (pin "2") (pinfunction "2_2") (pintype "passive"))
    )
    (net (code "9") (name "Net-(C206-Pad1)") (class "Default")
      (node (ref "C206") (pin "1") (pinfunction "1_1") (pintype "passive"))
      (node (ref "R216") (pin "1") (pinfunction "1_1") (pintype "passive"))
    )
    (net (code "10") (name "Net-(C207-Pad1)") (class "Default")
      (node (ref "C207") (pin "1") (pinfunction "1_1") (pintype "passive"))
      (node (ref "R218") (pin "1") (pinfunction "1_1") (pintype "passive"))
    )
    (net (code "11") (name "Net-(C209-Pad1)") (class "Default")
      (node (ref "C209") (pin "1") (pinfunction "1_1") (pintype "passive"))
      (node (ref "R219") (pin "1") (pinfunction "1_1") (pintype "passive"))
      (node (ref "R220") (pin "2") (pinfunction "2_2") (pintype "passive"))
    )
    (net (code "12") (name "Net-(CB110-1)") (class "Default")
      (node (ref "CB110") (pin "P$1") (pinfunction "1_P$1") (pintype "passive"))
      (node (ref "CB111") (pin "1") (pinfunction "1_1") (pintype "passive"))
      (node (ref "L101") (pin "P$2") (pinfunction "2_P$2") (pintype "passive"))
      (node (ref "L102") (pin "P$1") (pinfunction "1_P$1") (pintype "passive"))
    )
    (net (code "13") (name "Net-(CB112-1)") (class "Default")
      (node (ref "CB112") (pin "P$1") (pinfunction "1_P$1") (pintype "passive"))
      (node (ref "CB113") (pin "1") (pinfunction "1_1") (pintype "passive"))
      (node (ref "L103") (pin "P$2") (pinfunction "2_P$2") (pintype "passive"))
      (node (ref "L104") (pin "P$2") (pinfunction "2_P$2") (pintype "passive"))
    )
    (net (code "14") (name "Net-(CB114-Pad1)") (class "Default")
      (node (ref "CB114") (pin "1") (pinfunction "1_1") (pintype "passive"))
      (node (ref "CB115") (pin "1") (pinfunction "1_1") (pintype "passive"))
      (node (ref "R102") (pin "2") (pinfunction "2_2") (pintype "passive"))
      (node (ref "R104") (pin "1") (pinfunction "1_1") (pintype "passive"))
      (node (ref "R105") (pin "2") (pinfunction "2_2") (pintype "passive"))
      (node (ref "R106") (pin "1") (pinfunction "1_1") (pintype "passive"))
    )
    (net (code "15") (name "Net-(CB212-Pad2)") (class "Default")
      (node (ref "CB212") (pin "2") (pinfunction "2_2") (pintype "passive"))
      (node (ref "R212") (pin "2") (pinfunction "2_2") (pintype "passive"))
    )
    (net (code "16") (name "Net-(CB213-Pad2)") (class "Default")
      (node (ref "CB213") (pin "2") (pinfunction "2_2") (pintype "passive"))
      (node (ref "R213") (pin "2") (pinfunction "2_2") (pintype "passive"))
    )
    (net (code "17") (name "Net-(CB221-Pad1)") (class "Default")
      (node (ref "CB221") (pin "1") (pinfunction "1_1") (pintype "passive"))
      (node (ref "FB201") (pin "2") (pinfunction "2_2") (pintype "passive"))
      (node (ref "R203") (pin "1") (pinfunction "1_1") (pintype "passive"))
      (node (ref "R205") (pin "1") (pinfunction "1_1") (pintype "passive"))
    )
    (net (code "18") (name "Net-(CH1-2)") (class "Default")
      (node (ref "12VIN2") (pin "2") (pinfunction "2_2") (pintype "passive"))
      (node (ref "CH1") (pin "P$2") (pinfunction "2_P$2") (pintype "passive"))
    )
    (net (code "19") (name "Net-(CH1-3)") (class "Default")
      (node (ref "12VIN2") (pin "1") (pinfunction "1_1") (pintype "passive"))
      (node (ref "CH1") (pin "P$3") (pinfunction "3_P$3") (pintype "passive"))
    )
    (net (code "20") (name "Net-(CH2-2)") (class "Default")
      (node (ref "CH2") (pin "P$2") (pinfunction "2_P$2") (pintype "passive"))
      (node (ref "VDIN") (pin "2") (pinfunction "2_2") (pintype "passive"))
    )
    (net (code "21") (name "Net-(CH2-3)") (class "Default")
      (node (ref "CH2") (pin "P$3") (pinfunction "3_P$3") (pintype "passive"))
      (node (ref "VDIN") (pin "1") (pinfunction "1_1") (pintype "passive"))
    )
    (net (code "22") (name "Net-(CH3-2)") (class "Default")
      (node (ref "12VIN") (pin "2") (pinfunction "2_2") (pintype "passive"))
      (node (ref "CH3") (pin "P$2") (pinfunction "2_P$2") (pintype "passive"))
    )
    (net (code "23") (name "Net-(CH3-3)") (class "Default")
      (node (ref "12VIN") (pin "1") (pinfunction "1_1") (pintype "passive"))
      (node (ref "CH3") (pin "P$3") (pinfunction "3_P$3") (pintype "passive"))
    )
    (net (code "24") (name "Net-(CH4-1)") (class "Default")
      (node (ref "CH4") (pin "P$1") (pinfunction "1_P$1") (pintype "passive"))
      (node (ref "TPA_EN") (pin "1") (pinfunction "1_1") (pintype "passive"))
    )
    (net (code "25") (name "Net-(CH4-3)") (class "Default")
      (node (ref "CH4") (pin "P$3") (pinfunction "3_P$3") (pintype "passive"))
      (node (ref "Q3") (pin "1") (pinfunction "G_1") (pintype "passive"))
      (node (ref "R109") (pin "2") (pinfunction "2_2") (pintype "passive"))
      (node (ref "U102") (pin "2") (pinfunction "I1_2") (pintype "input"))
      (node (ref "U103") (pin "2") (pinfunction "I1_2") (pintype "input"))
    )
    (net (code "26") (name "Net-(CH4-4)") (class "Default")
      (node (ref "CH4") (pin "P$4") (pinfunction "4_P$4") (pintype "passive"))
      (node (ref "TPA_EN") (pin "2") (pinfunction "2_2") (pintype "passive"))
    )
    (net (code "27") (name "Net-(CH5-1)") (class "Default")
      (node (ref "CH5") (pin "P$1") (pinfunction "1_P$1") (pintype "passive"))
      (node (ref "VSET") (pin "1") (pinfunction "1_1") (pintype "passive"))
    )
    (net (code "28") (name "Net-(CH5-3)") (class "Default")
      (node (ref "CH5") (pin "P$3") (pinfunction "3_P$3") (pintype "passive"))
      (node (ref "R219") (pin "2") (pinfunction "2_2") (pintype "passive"))
      (node (ref "R221") (pin "1") (pinfunction "1_1") (pintype "passive"))
    )
    (net (code "29") (name "Net-(CH5-4)") (class "Default")
      (node (ref "CH5") (pin "P$4") (pinfunction "4_P$4") (pintype "passive"))
      (node (ref "VSET") (pin "2") (pinfunction "2_2") (pintype "passive"))
    )
    (net (code "30") (name "Net-(CH6-1)") (class "Default")
      (node (ref "CH6") (pin "P$1") (pinfunction "1_P$1") (pintype "passive"))
      (node (ref "SHDN") (pin "1") (pinfunction "1_1") (pintype "passive"))
    )
    (net (code "31") (name "Net-(CH6-3)") (class "Default")
      (node (ref "CH6") (pin "P$3") (pinfunction "3_P$3") (pintype "passive"))
      (node (ref "PWM") (pin "1") (pinfunction "ILIM_1") (pintype "input"))
      (node (ref "Q6") (pin "1") (pinfunction "G_1") (pintype "passive"))
      (node (ref "R201") (pin "2") (pinfunction "2_2") (pintype "passive"))
      (node (ref "U203") (pin "2") (pinfunction "I1_2") (pintype "input"))
    )
    (net (code "32") (name "Net-(CH6-4)") (class "Default")
      (node (ref "CH6") (pin "P$4") (pinfunction "4_P$4") (pintype "passive"))
      (node (ref "SHDN") (pin "2") (pinfunction "2_2") (pintype "passive"))
    )
    (net (code "33") (name "Net-(COMP1-+IN)") (class "Default")
      (node (ref "COMP1") (pin "2") (pinfunction "+IN_2") (pintype "input"))
      (node (ref "R106") (pin "2") (pinfunction "2_2") (pintype "passive"))
      (node (ref "R107") (pin "1") (pinfunction "1_1") (pintype "passive"))
    )
    (net (code "34") (name "Net-(COMP1--IN)") (class "Default")
      (node (ref "C101") (pin "2") (pinfunction "2_2") (pintype "passive"))
      (node (ref "COMP1") (pin "3") (pinfunction "-IN_3") (pintype "input"))
      (node (ref "R102") (pin "1") (pinfunction "1_1") (pintype "passive"))
      (node (ref "R103") (pin "1") (pinfunction "1_1") (pintype "passive"))
    )
    (net (code "35") (name "Net-(COMP1-LATCH)") (class "Default")
      (node (ref "COMP1") (pin "5") (pinfunction "LATCH_5") (pintype "input"))
      (node (ref "Q3") (pin "3") (pinfunction "D_3") (pintype "passive"))
      (node (ref "R108") (pin "2") (pinfunction "2_2") (pintype "passive"))
    )
    (net (code "36") (name "Net-(COMP1-Q)") (class "Default")
      (node (ref "COMP1") (pin "7") (pinfunction "Q_7") (pintype "output"))
      (node (ref "R107") (pin "2") (pinfunction "2_2") (pintype "passive"))
      (node (ref "U102") (pin "1") (pinfunction "I0_1") (pintype "input"))
    )
    (net (code "37") (name "Net-(COMP1-~{Q})") (class "Default")
      (node (ref "COMP1") (pin "8") (pinfunction "~{Q}_8") (pintype "output"))
      (node (ref "U103") (pin "1") (pinfunction "I0_1") (pintype "input"))
    )
    (net (code "38") (name "Net-(D202-PadC)") (class "Default")
      (node (ref "D202") (pin "C") (pinfunction "C_C") (pintype "passive"))
      (node (ref "R208") (pin "1") (pinfunction "1_1") (pintype "passive"))
    )
    (net (code "39") (name "Net-(D203-PadC)") (class "Default")
      (node (ref "D203") (pin "C") (pinfunction "C_C") (pintype "passive"))
      (node (ref "R209") (pin "1") (pinfunction "1_1") (pintype "passive"))
    )
    (net (code "40") (name "Net-(FB202-2)") (class "Default")
      (node (ref "CB203") (pin "+") (pinfunction "+_+") (pintype "passive"))
      (node (ref "CB204") (pin "1") (pinfunction "1_1") (pintype "passive"))
      (node (ref "CB205") (pin "1") (pinfunction "1_1") (pintype "passive"))
      (node (ref "CB206") (pin "1") (pinfunction "1_1") (pintype "passive"))
      (node (ref "FB202") (pin "P$2") (pinfunction "2_P$2") (pintype "passive"))
      (node (ref "Q4") (pin "3") (pinfunction "D_3") (pintype "passive"))
      (node (ref "Q4") (pin "5") (pinfunction "D1_5") (pintype "passive"))
    )
    (net (code "41") (name "Net-(L201-1)") (class "Default")
      (node (ref "CB219") (pin "2") (pinfunction "2_2") (pintype "passive"))
      (node (ref "L201") (pin "P$1") (pinfunction "1_P$1") (pintype "passive"))
      (node (ref "Q4") (pin "2") (pinfunction "S1_2") (pintype "passive"))
      (node (ref "Q4") (pin "4") (pinfunction "S2_4") (pintype "passive"))
      (node (ref "Q5") (pin "3") (pinfunction "D_3") (pintype "passive"))
      (node (ref "Q5") (pin "5") (pinfunction "D1_5") (pintype "passive"))
      (node (ref "U201") (pin "5") (pinfunction "HS_5") (pintype "passive"))
    )
    (net (code "42") (name "Net-(L201-2)") (class "Default")
      (node (ref "CB212") (pin "1") (pinfunction "1_1") (pintype "passive"))
      (node (ref "CB213") (pin "1") (pinfunction "1_1") (pintype "passive"))
      (node (ref "L201") (pin "P$2") (pinfunction "2_P$2") (pintype "passive"))
      (node (ref "R214") (pin "2") (pinfunction "2_2") (pintype "passive"))
      (node (ref "VDOUT") (pin "2") (pinfunction "2_2") (pintype "passive"))
    )
    (net (code "43") (name "Net-(OP1A-+IN)") (class "Default")
      (node (ref "OP1") (pin "3") (pinfunction "+IN_3") (pintype "input"))
      (node (ref "R214") (pin "1") (pinfunction "1_1") (pintype "passive"))
      (node (ref "R215") (pin "2") (pinfunction "2_2") (pintype "passive"))
    )
    (net (code "44") (name "Net-(OP1A--IN)") (class "Default")
      (node (ref "C206") (pin "2") (pinfunction "2_2") (pintype "passive"))
      (node (ref "OP1") (pin "1") (pinfunction "OUT_1") (pintype "output"))
      (node (ref "OP1") (pin "4") (pinfunction "-IN_4") (pintype "input"))
      (node (ref "R217") (pin "1") (pinfunction "1_1") (pintype "passive"))
    )
    (net (code "45") (name "Net-(OP2A-+IN)") (class "Default")
      (node (ref "C210") (pin "1") (pinfunction "1_1") (pintype "passive"))
      (node (ref "OP2") (pin "3") (pinfunction "+IN_3") (pintype "input"))
      (node (ref "R220") (pin "1") (pinfunction "1_1") (pintype "passive"))
    )
    (net (code "46") (name "Net-(OP2A--IN)") (class "Default")
      (node (ref "C207") (pin "2") (pinfunction "2_2") (pintype "passive"))
      (node (ref "C208") (pin "2") (pinfunction "2_2") (pintype "passive"))
      (node (ref "OP2") (pin "4") (pinfunction "-IN_4") (pintype "input"))
      (node (ref "R216") (pin "2") (pinfunction "2_2") (pintype "passive"))
      (node (ref "R217") (pin "2") (pinfunction "2_2") (pintype "passive"))
    )
    (net (code "47") (name "Net-(OP2A-OUT)") (class "Default")
      (node (ref "C208") (pin "1") (pinfunction "1_1") (pintype "passive"))
      (node (ref "OP2") (pin "1") (pinfunction "OUT_1") (pintype "output"))
      (node (ref "PWM") (pin "2") (pinfunction "FB_2") (pintype "input"))
      (node (ref "R218") (pin "2") (pinfunction "2_2") (pintype "passive"))
    )
    (net (code "48") (name "Net-(POT1-A)") (class "Default")
      (node (ref "C102") (pin "1") (pinfunction "1_1") (pintype "passive"))
      (node (ref "POT1") (pin "1") (pinfunction "A_1") (pintype "passive"))
      (node (ref "U101") (pin "6") (pinfunction "HI_6") (pintype "input"))
    )
    (net (code "49") (name "Net-(POT1-E)") (class "Default")
      (node (ref "POT1") (pin "2") (pinfunction "S_2") (pintype "passive"))
      (node (ref "POT1") (pin "3") (pinfunction "E_3") (pintype "passive"))
      (node (ref "U102") (pin "4") (pinfunction "O_4") (pintype "output"))
    )
    (net (code "50") (name "Net-(POT2-A)") (class "Default")
      (node (ref "C103") (pin "1") (pinfunction "1_1") (pintype "passive"))
      (node (ref "POT2") (pin "1") (pinfunction "A_1") (pintype "passive"))
      (node (ref "U101") (pin "7") (pinfunction "LI_7") (pintype "input"))
    )
    (net (code "51") (name "Net-(POT2-E)") (class "Default")
      (node (ref "POT2") (pin "2") (pinfunction "S_2") (pintype "passive"))
      (node (ref "POT2") (pin "3") (pinfunction "E_3") (pintype "passive"))
      (node (ref "U103") (pin "4") (pinfunction "O_4") (pintype "output"))
    )
    (net (code "52") (name "Net-(POT3-A)") (class "Default")
      (node (ref "C204") (pin "1") (pinfunction "1_1") (pintype "passive"))
      (node (ref "D202") (pin "A") (pinfunction "A_A") (pintype "passive"))
      (node (ref "POT3") (pin "1") (pinfunction "A_1") (pintype "passive"))
      (node (ref "U201") (pin "6") (pinfunction "HI_6") (pintype "input"))
    )
    (net (code "53") (name "Net-(POT3-E)") (class "Default")
      (node (ref "POT3") (pin "2") (pinfunction "S_2") (pintype "passive"))
      (node (ref "POT3") (pin "3") (pinfunction "E_3") (pintype "passive"))
      (node (ref "R208") (pin "2") (pinfunction "2_2") (pintype "passive"))
      (node (ref "U202") (pin "4") (pinfunction "O_4") (pintype "output"))
    )
    (net (code "54") (name "Net-(POT4-A)") (class "Default")
      (node (ref "C205") (pin "1") (pinfunction "1_1") (pintype "passive"))
      (node (ref "D203") (pin "A") (pinfunction "A_A") (pintype "passive"))
      (node (ref "POT4") (pin "1") (pinfunction "A_1") (pintype "passive"))
      (node (ref "U201") (pin "7") (pinfunction "LI_7") (pintype "input"))
    )
    (net (code "55") (name "Net-(POT4-E)") (class "Default")
      (node (ref "POT4") (pin "2") (pinfunction "S_2") (pintype "passive"))
      (node (ref "POT4") (pin "3") (pinfunction "E_3") (pintype "passive"))
      (node (ref "R209") (pin "2") (pinfunction "2_2") (pintype "passive"))
      (node (ref "U203") (pin "4") (pinfunction "O_4") (pintype "output"))
    )
    (net (code "56") (name "Net-(PWM-OUT)") (class "Default")
      (node (ref "C203") (pin "1") (pinfunction "1_1") (pintype "passive"))
      (node (ref "PWM") (pin "7") (pinfunction "OUT_7") (pintype "output"))
      (node (ref "R206") (pin "2") (pinfunction "2_2") (pintype "passive"))
    )
    (net (code "57") (name "Net-(PWM-RC)") (class "Default")
      (node (ref "C202") (pin "1") (pinfunction "1_1") (pintype "passive"))
      (node (ref "PWM") (pin "5") (pinfunction "RC_5") (pintype "passive"))
      (node (ref "R205") (pin "2") (pinfunction "2_2") (pintype "passive"))
    )
    (net (code "58") (name "Net-(PWM-VFF)") (class "Default")
      (node (ref "C201") (pin "1") (pinfunction "1_1") (pintype "passive"))
      (node (ref "PWM") (pin "3") (pinfunction "VFF_3") (pintype "passive"))
      (node (ref "R202") (pin "1") (pinfunction "1_1") (pintype "passive"))
      (node (ref "R203") (pin "2") (pinfunction "2_2") (pintype "passive"))
      (node (ref "R204") (pin "1") (pinfunction "1_1") (pintype "passive"))
    )
    (net (code "59") (name "Net-(Q1-G)") (class "Default")
      (node (ref "Q1") (pin "1") (pinfunction "G_1") (pintype "passive"))
      (node (ref "R112") (pin "2") (pinfunction "2_2") (pintype "passive"))
    )
    (net (code "60") (name "Net-(Q2-G)") (class "Default")
      (node (ref "Q2") (pin "1") (pinfunction "G_1") (pintype "passive"))
      (node (ref "R114") (pin "2") (pinfunction "2_2") (pintype "passive"))
    )
    (net (code "61") (name "Net-(Q4-G)") (class "Default")
      (node (ref "Q4") (pin "1") (pinfunction "G_1") (pintype "passive"))
      (node (ref "R210") (pin "2") (pinfunction "2_2") (pintype "passive"))
      (node (ref "U201") (pin "4") (pinfunction "HOL_4") (pintype "output"))
    )
    (net (code "62") (name "Net-(Q5-G)") (class "Default")
      (node (ref "Q5") (pin "1") (pinfunction "G_1") (pintype "passive"))
      (node (ref "R211") (pin "2") (pinfunction "2_2") (pintype "passive"))
      (node (ref "U201") (pin "9") (pinfunction "LOL_9") (pintype "output"))
    )
    (net (code "63") (name "Net-(Q6-D)") (class "Default")
      (node (ref "Q6") (pin "3") (pinfunction "D_3") (pintype "passive"))
      (node (ref "R202") (pin "2") (pinfunction "2_2") (pintype "passive"))
    )
    (net (code "64") (name "Net-(T1-6)") (class "Default")
      (node (ref "T1") (pin "S1") (pinfunction "6_S1") (pintype "passive"))
      (node (ref "TPA_OUT") (pin "S1") (pinfunction "GND1_S1") (pintype "power_in"))
      (node (ref "TPA_OUT") (pin "S2") (pinfunction "GND2_S2") (pintype "power_in"))
    )
    (net (code "65") (name "Net-(TPA_IN-1)") (class "Default")
      (node (ref "C101") (pin "1") (pinfunction "1_1") (pintype "passive"))
      (node (ref "R101") (pin "1") (pinfunction "1_1") (pintype "passive"))
      (node (ref "TPA_IN") (pin "I") (pinfunction "1_I") (pintype "passive"))
    )
    (net (code "66") (name "Net-(U101-HB)") (class "Default")
      (node (ref "CB107") (pin "1") (pinfunction "1_1") (pintype "passive"))
      (node (ref "R110") (pin "1") (pinfunction "1_1") (pintype "passive"))
      (node (ref "U101") (pin "2") (pinfunction "HB_2") (pintype "passive"))
    )
    (net (code "67") (name "Net-(U101-HOH)") (class "Default")
      (node (ref "R111") (pin "1") (pinfunction "1_1") (pintype "passive"))
      (node (ref "U101") (pin "3") (pinfunction "HOH_3") (pintype "output"))
    )
    (net (code "68") (name "Net-(U101-HOL)") (class "Default")
      (node (ref "R111") (pin "2") (pinfunction "2_2") (pintype "passive"))
      (node (ref "R112") (pin "1") (pinfunction "1_1") (pintype "passive"))
      (node (ref "U101") (pin "4") (pinfunction "HOL_4") (pintype "output"))
    )
    (net (code "69") (name "Net-(U101-LOH)") (class "Default")
      (node (ref "R113") (pin "1") (pinfunction "1_1") (pintype "passive"))
      (node (ref "U101") (pin "10") (pinfunction "LOH_10") (pintype "output"))
    )
    (net (code "70") (name "Net-(U101-LOL)") (class "Default")
      (node (ref "R113") (pin "2") (pinfunction "2_2") (pintype "passive"))
      (node (ref "R114") (pin "1") (pinfunction "1_1") (pintype "passive"))
      (node (ref "U101") (pin "9") (pinfunction "LOL_9") (pintype "output"))
    )
    (net (code "71") (name "Net-(U201-HB)") (class "Default")
      (node (ref "CB219") (pin "1") (pinfunction "1_1") (pintype "passive"))
      (node (ref "U201") (pin "2") (pinfunction "HB_2") (pintype "passive"))
    )
    (net (code "72") (name "Net-(U201-HOH)") (class "Default")
      (node (ref "R210") (pin "1") (pinfunction "1_1") (pintype "passive"))
      (node (ref "U201") (pin "3") (pinfunction "HOH_3") (pintype "output"))
    )
    (net (code "73") (name "Net-(U201-LOH)") (class "Default")
      (node (ref "R211") (pin "1") (pinfunction "1_1") (pintype "passive"))
      (node (ref "U201") (pin "10") (pinfunction "LOH_10") (pintype "output"))
    )
    (net (code "74") (name "Net-(U202A-I0)") (class "Default")
      (node (ref "D201") (pin "A") (pinfunction "A_A") (pintype "passive"))
      (node (ref "R207") (pin "1") (pinfunction "1_1") (pintype "passive"))
      (node (ref "U202") (pin "1") (pinfunction "I0_1") (pintype "input"))
      (node (ref "U202") (pin "2") (pinfunction "I1_2") (pintype "input"))
      (node (ref "U203") (pin "1") (pinfunction "I0_1") (pintype "input"))
    )
    (net (code "75") (name "VCC") (class "Default")
      (node (ref "CB209") (pin "1") (pinfunction "1_1") (pintype "passive"))
      (node (ref "CB214") (pin "1") (pinfunction "1_1") (pintype "passive"))
      (node (ref "CB215") (pin "1") (pinfunction "1_1") (pintype "passive"))
      (node (ref "CB216") (pin "1") (pinfunction "1_1") (pintype "passive"))
      (node (ref "OP1") (pin "5") (pinfunction "V+_5") (pintype "power_in"))
      (node (ref "OP2") (pin "5") (pinfunction "V+_5") (pintype "power_in"))
      (node (ref "PWM") (pin "8") (pinfunction "VDD_8") (pintype "power_in"))
      (node (ref "U204") (pin "3") (pinfunction "OUT_3") (pintype "passive"))
    )
    (net (code "76") (name "VDRAIN") (class "Default")
      (node (ref "CB116") (pin "1") (pinfunction "1_1") (pintype "passive"))
      (node (ref "CH2") (pin "P$4") (pinfunction "4_P$4") (pintype "passive"))
      (node (ref "L101") (pin "P$1") (pinfunction "1_P$1") (pintype "passive"))
      (node (ref "L103") (pin "P$1") (pinfunction "1_P$1") (pintype "passive"))
    )
    (net (code "77") (name "unconnected-(T1-5-PadCT)") (class "Default")
      (node (ref "T1") (pin "CT") (pinfunction "5_CT") (pintype "passive"))
    )
  )
)
